# M_ch_Ph_t.net
KiCad netlist of a schematic drawn in Altium Designer
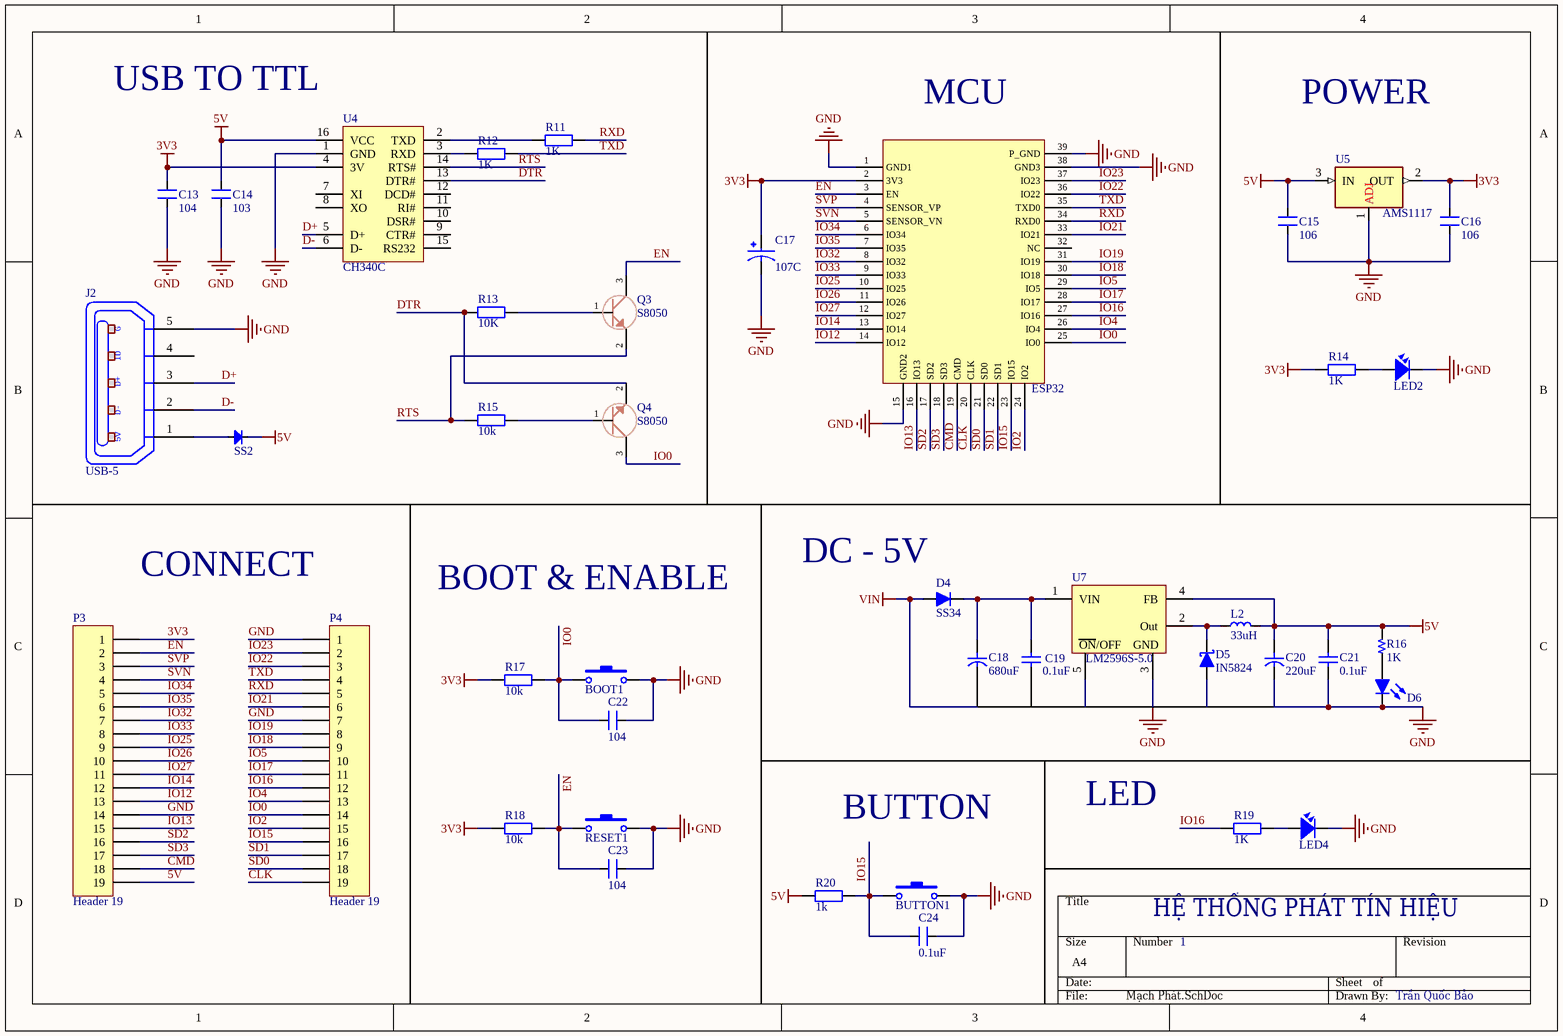
[diagram p0: Mạch Phát.SchDoc]

(export (version "E")
  (design (tool "Eeschema 10.0.6"))
  (components
    (comp (ref "BOOT1")
      (value "SW-SMD")
      (footprint "SW-SMD")
      (description "Switch")
      (fields (field (name "PUBLISHER") "Altium Limited"))
      (libsource (lib "My Library") (part "SW-SMD"))
    )
    (comp (ref "BUTTON1")
      (value "SW-SMD")
      (footprint "SW-SMD")
      (description "Switch")
      (fields (field (name "PUBLISHER") "Altium Limited"))
      (libsource (lib "My Library") (part "SW-SMD"))
    )
    (comp (ref "C13")
      (value "104")
      (footprint "SM-0805")
      (description "Cap SMD")
      (libsource (lib "My Library") (part "CM"))
    )
    (comp (ref "C14")
      (value "103")
      (footprint "SM-0805")
      (description "Cap SMD")
      (libsource (lib "My Library") (part "CM"))
    )
    (comp (ref "C15")
      (value "106")
      (footprint "SM-0805")
      (description "Cap SMD")
      (libsource (lib "My Library") (part "CM"))
    )
    (comp (ref "C16")
      (value "106")
      (footprint "SM-0805")
      (description "Cap SMD")
      (libsource (lib "My Library") (part "CM"))
    )
    (comp (ref "C17")
      (value "107C")
      (footprint "CAP_TANTALUM_3528")
      (description "Capacitor, Tantalum")
      (fields (field (name "MF") "AVX") (field (name "MP") "TAJB475K025RNJ"))
      (libsource (lib "My Library") (part "CAP_TANTALUM_SMD"))
    )
    (comp (ref "C18")
      (value "680uF")
      (footprint "C SMD TAN 1206 (A)")
      (description "Capacitor pol")
      (libsource (lib "chipfc_altium_libs") (part "Capacitor"))
    )
    (comp (ref "C19")
      (value "0.1uF")
      (footprint "C 0805")
      (description "Capacitor non-pol")
      (libsource (lib "chipfc_altium_libs") (part "Capacitor NP"))
    )
    (comp (ref "C20")
      (value "220uF")
      (footprint "C SMD TAN 1206 (A)")
      (description "Capacitor pol")
      (libsource (lib "chipfc_altium_libs") (part "Capacitor"))
    )
    (comp (ref "C21")
      (value "0.1uF")
      (footprint "C 0805")
      (description "Capacitor non-pol")
      (libsource (lib "chipfc_altium_libs") (part "Capacitor NP"))
    )
    (comp (ref "C22")
      (value "104")
      (footprint "SM-0805")
      (description "Cap SMD")
      (libsource (lib "My Library") (part "CM"))
    )
    (comp (ref "C23")
      (value "104")
      (footprint "SM-0805")
      (description "Cap SMD")
      (libsource (lib "My Library") (part "CM"))
    )
    (comp (ref "C24")
      (value "0.1uF")
      (footprint "SM-0805")
      (description "Cap SMD")
      (libsource (lib "My Library") (part "CM"))
    )
    (comp (ref "D4")
      (value "SS34")
      (footprint "DO-35 (SOD27 )")
      (description "Default Diode")
      (libsource (lib "chipfc_altium_libs") (part "Diode"))
    )
    (comp (ref "D5")
      (value "IN5824")
      (footprint "DO-41")
      (description "Schottky Diode")
      (libsource (lib "chipfc_altium_libs") (part "Diode Schottky"))
    )
    (comp (ref "D6")
      (value "Led")
      (footprint "Led 0805 RED")
      (description "Typical LED")
      (libsource (lib "chipfc_altium_libs") (part "Led"))
    )
    (comp (ref "ESP32")
      (value "ESP32")
      (footprint "My Library:ESP_WROOM_32")
      (libsource (lib "My Library") (part "ESP-WROOM-32"))
    )
    (comp (ref "J2")
      (value "USB-5")
      (footprint "USB-M1")
      (fields
        (field (name "MANUFACTURER") "FCI")
        (field (name "MANUFACTURER PART NUMBER") "10118193-0001LF")
        (field (name ".CREATOR") "MM")
        (field (name ".CHECKED PCB") "RF")
        (field (name ".CHECKED SCH") "MM")
      )
      (libsource (lib "My Library") (part "USB-5"))
    )
    (comp (ref "L2")
      (value "33uH")
      (footprint "Inductor SMD 12x12x8")
      (description "Inductor")
      (libsource (lib "chipfc_altium_libs") (part "Inductor"))
    )
    (comp (ref "LED2") (value "LED") (footprint "LED 3512") (libsource (lib "My Library") (part "LED SMD")))
    (comp (ref "LED4") (value "LED") (footprint "LED 3512") (libsource (lib "My Library") (part "LED SMD")))
    (comp (ref "P3")
      (value "Header 19")
      (footprint "HDR1X19")
      (description "Header, 19-Pin")
      (fields (field (name "PUBLISHER") "Altium Limited"))
      (libsource (lib "My Library") (part "Header 19"))
    )
    (comp (ref "P4")
      (value "Header 19")
      (footprint "HDR1X19")
      (description "Header, 19-Pin")
      (fields (field (name "PUBLISHER") "Altium Limited"))
      (libsource (lib "") (part "Header 19_1"))
    )
    (comp (ref "Q3")
      (value "S8050")
      (footprint "SOT23")
      (libsource (lib "My Library") (part "Transitor SMD"))
    )
    (comp (ref "Q4")
      (value "S8050")
      (footprint "SOT23")
      (libsource (lib "My Library") (part "Transitor SMD"))
    )
    (comp (ref "R11")
      (value "1K")
      (footprint "DIEN TRO 0805")
      (description "Resistor SMD 0805")
      (fields (field (name "Comment") "R0805") (field (name "PUBLISHER") "Altium Limited"))
      (libsource (lib "My Library") (part "R0805"))
    )
    (comp (ref "R12")
      (value "1K")
      (footprint "DIEN TRO 0805")
      (description "Resistor SMD 0805")
      (fields (field (name "Comment") "R0805") (field (name "PUBLISHER") "Altium Limited"))
      (libsource (lib "My Library") (part "R0805"))
    )
    (comp (ref "R13")
      (value "10K")
      (footprint "DIEN TRO 0805")
      (description "Resistor SMD 0805")
      (fields (field (name "Comment") "R0805") (field (name "PUBLISHER") "Altium Limited"))
      (libsource (lib "My Library") (part "R0805"))
    )
    (comp (ref "R14")
      (value "1K")
      (footprint "DIEN TRO 0805")
      (description "Resistor SMD 0805")
      (fields (field (name "Comment") "R0805") (field (name "PUBLISHER") "Altium Limited"))
      (libsource (lib "My Library") (part "R0805"))
    )
    (comp (ref "R15")
      (value "10k")
      (footprint "DIEN TRO 0805")
      (description "Resistor SMD 0805")
      (fields (field (name "Comment") "R0805") (field (name "PUBLISHER") "Altium Limited"))
      (libsource (lib "My Library") (part "R0805"))
    )
    (comp (ref "R16")
      (value "1K")
      (footprint "R 0805")
      (description "Resistor")
      (libsource (lib "chipfc_altium_libs") (part "Resistor"))
    )
    (comp (ref "R17")
      (value "10k")
      (footprint "DIEN TRO 0805")
      (description "Resistor SMD 0805")
      (fields (field (name "Comment") "R0805") (field (name "PUBLISHER") "Altium Limited"))
      (libsource (lib "My Library") (part "R0805"))
    )
    (comp (ref "R18")
      (value "10k")
      (footprint "DIEN TRO 0805")
      (description "Resistor SMD 0805")
      (fields (field (name "Comment") "R0805") (field (name "PUBLISHER") "Altium Limited"))
      (libsource (lib "My Library") (part "R0805"))
    )
    (comp (ref "R19")
      (value "1K")
      (footprint "DIEN TRO 0805")
      (description "Resistor SMD 0805")
      (fields (field (name "Comment") "R0805") (field (name "PUBLISHER") "Altium Limited"))
      (libsource (lib "My Library") (part "R0805"))
    )
    (comp (ref "R20")
      (value "1k")
      (footprint "DIEN TRO 0805")
      (description "Resistor SMD 0805")
      (fields (field (name "Comment") "R0805") (field (name "PUBLISHER") "Altium Limited"))
      (libsource (lib "My Library") (part "R0805"))
    )
    (comp (ref "RESET1")
      (value "SW-SMD")
      (footprint "SW-SMD")
      (description "Switch")
      (fields (field (name "PUBLISHER") "Altium Limited"))
      (libsource (lib "My Library") (part "SW-SMD"))
    )
    (comp (ref "SS2")
      (value "Diode SMD")
      (footprint "DIO-SMD-106")
      (description "Default Diode")
      (fields (field (name "PUBLISHER") "Altium Limited"))
      (libsource (lib "My Library") (part "Diode SMD"))
    )
    (comp (ref "U4")
      (value "CH340C")
      (footprint "SO16")
      (description "High and Low Side Driver")
      (fields (field (name "PUBLISHER") "Altium Limited"))
      (libsource (lib "My Library") (part "CH340G"))
    )
    (comp (ref "U5")
      (value "AMS1117")
      (footprint "SOT223-4N")
      (description "IC")
      (libsource (lib "My Library") (part "AMS1117"))
    )
    (comp (ref "U7")
      (value "LM2596S-5.0")
      (footprint "TO-263-5")
      (description "Simple Switcher 3A Step-Down Voltage Regulator")
      (libsource (lib "chipfc_altium_libs") (part "LM2596S-5.0"))
    )
  )
  (nets
    (net (code "1") (name "/CLK") (class "Default")
      (node (ref "ESP32") (pin "20") (pinfunction "CLK_20") (pintype "passive"))
      (node (ref "P4") (pin "19") (pinfunction "19_19") (pintype "passive"))
    )
    (net (code "2") (name "/CMD") (class "Default")
      (node (ref "ESP32") (pin "19") (pinfunction "CMD_19") (pintype "passive"))
      (node (ref "P3") (pin "18") (pinfunction "18_18") (pintype "passive"))
    )
    (net (code "3") (name "/D+") (class "Default")
      (node (ref "J2") (pin "3") (pinfunction "P3_3") (pintype "passive"))
      (node (ref "U4") (pin "5") (pinfunction "D+_5") (pintype "passive"))
    )
    (net (code "4") (name "/D-") (class "Default")
      (node (ref "J2") (pin "2") (pinfunction "P2_2") (pintype "passive"))
      (node (ref "U4") (pin "6") (pinfunction "D-_6") (pintype "passive"))
    )
    (net (code "5") (name "/DTR") (class "Default")
      (node (ref "Q4") (pin "2") (pinfunction "E_2") (pintype "passive"))
      (node (ref "R13") (pin "1") (pinfunction "1_1") (pintype "passive"))
      (node (ref "U4") (pin "13") (pinfunction "DTR#_13") (pintype "passive"))
    )
    (net (code "6") (name "/EN") (class "Default")
      (node (ref "C23") (pin "2") (pinfunction "2_2") (pintype "passive"))
      (node (ref "ESP32") (pin "3") (pinfunction "EN_3") (pintype "passive"))
      (node (ref "P3") (pin "2") (pinfunction "2_2") (pintype "passive"))
      (node (ref "Q3") (pin "3") (pinfunction "C_3") (pintype "passive"))
      (node (ref "R18") (pin "2") (pinfunction "2_2") (pintype "passive"))
      (node (ref "RESET1") (pin "1") (pinfunction "1_1") (pintype "passive"))
    )
    (net (code "7") (name "/IO0") (class "Default")
      (node (ref "BOOT1") (pin "1") (pinfunction "1_1") (pintype "passive"))
      (node (ref "C22") (pin "2") (pinfunction "2_2") (pintype "passive"))
      (node (ref "ESP32") (pin "25") (pinfunction "IO0_25") (pintype "passive"))
      (node (ref "P4") (pin "14") (pinfunction "14_14") (pintype "passive"))
      (node (ref "Q4") (pin "3") (pinfunction "C_3") (pintype "passive"))
      (node (ref "R17") (pin "2") (pinfunction "2_2") (pintype "passive"))
    )
    (net (code "8") (name "/IO2") (class "Default")
      (node (ref "ESP32") (pin "24") (pinfunction "IO2_24") (pintype "passive"))
      (node (ref "P4") (pin "15") (pinfunction "15_15") (pintype "passive"))
    )
    (net (code "9") (name "/IO4") (class "Default")
      (node (ref "ESP32") (pin "26") (pinfunction "IO4_26") (pintype "passive"))
      (node (ref "P4") (pin "13") (pinfunction "13_13") (pintype "passive"))
    )
    (net (code "10") (name "/IO5") (class "Default")
      (node (ref "ESP32") (pin "29") (pinfunction "IO5_29") (pintype "passive"))
      (node (ref "P4") (pin "10") (pinfunction "10_10") (pintype "passive"))
    )
    (net (code "11") (name "/IO12") (class "Default")
      (node (ref "ESP32") (pin "14") (pinfunction "IO12_14") (pintype "passive"))
      (node (ref "P3") (pin "13") (pinfunction "13_13") (pintype "passive"))
    )
    (net (code "12") (name "/IO13") (class "Default")
      (node (ref "ESP32") (pin "16") (pinfunction "IO13_16") (pintype "passive"))
      (node (ref "P3") (pin "15") (pinfunction "15_15") (pintype "passive"))
    )
    (net (code "13") (name "/IO14") (class "Default")
      (node (ref "ESP32") (pin "13") (pinfunction "IO14_13") (pintype "passive"))
      (node (ref "P3") (pin "12") (pinfunction "12_12") (pintype "passive"))
    )
    (net (code "14") (name "/IO15") (class "Default")
      (node (ref "BUTTON1") (pin "1") (pinfunction "1_1") (pintype "passive"))
      (node (ref "C24") (pin "2") (pinfunction "2_2") (pintype "passive"))
      (node (ref "ESP32") (pin "23") (pinfunction "IO15_23") (pintype "passive"))
      (node (ref "P4") (pin "16") (pinfunction "16_16") (pintype "passive"))
      (node (ref "R20") (pin "2") (pinfunction "2_2") (pintype "passive"))
    )
    (net (code "15") (name "/IO16") (class "Default")
      (node (ref "ESP32") (pin "27") (pinfunction "IO16_27") (pintype "passive"))
      (node (ref "P4") (pin "12") (pinfunction "12_12") (pintype "passive"))
      (node (ref "R19") (pin "1") (pinfunction "1_1") (pintype "passive"))
    )
    (net (code "16") (name "/IO17") (class "Default")
      (node (ref "ESP32") (pin "28") (pinfunction "IO17_28") (pintype "passive"))
      (node (ref "P4") (pin "11") (pinfunction "11_11") (pintype "passive"))
    )
    (net (code "17") (name "/IO18") (class "Default")
      (node (ref "ESP32") (pin "30") (pinfunction "IO18_30") (pintype "passive"))
      (node (ref "P4") (pin "9") (pinfunction "9_9") (pintype "passive"))
    )
    (net (code "18") (name "/IO19") (class "Default")
      (node (ref "ESP32") (pin "31") (pinfunction "IO19_31") (pintype "passive"))
      (node (ref "P4") (pin "8") (pinfunction "8_8") (pintype "passive"))
    )
    (net (code "19") (name "/IO21") (class "Default")
      (node (ref "ESP32") (pin "33") (pinfunction "IO21_33") (pintype "passive"))
      (node (ref "P4") (pin "6") (pinfunction "6_6") (pintype "passive"))
    )
    (net (code "20") (name "/IO22") (class "Default")
      (node (ref "ESP32") (pin "36") (pinfunction "IO22_36") (pintype "passive"))
      (node (ref "P4") (pin "3") (pinfunction "3_3") (pintype "passive"))
    )
    (net (code "21") (name "/IO23") (class "Default")
      (node (ref "ESP32") (pin "37") (pinfunction "IO23_37") (pintype "passive"))
      (node (ref "P4") (pin "2") (pinfunction "2_2") (pintype "passive"))
    )
    (net (code "22") (name "/IO25") (class "Default")
      (node (ref "ESP32") (pin "10") (pinfunction "IO25_10") (pintype "passive"))
      (node (ref "P3") (pin "9") (pinfunction "9_9") (pintype "passive"))
    )
    (net (code "23") (name "/IO26") (class "Default")
      (node (ref "ESP32") (pin "11") (pinfunction "IO26_11") (pintype "passive"))
      (node (ref "P3") (pin "10") (pinfunction "10_10") (pintype "passive"))
    )
    (net (code "24") (name "/IO27") (class "Default")
      (node (ref "ESP32") (pin "12") (pinfunction "IO27_12") (pintype "passive"))
      (node (ref "P3") (pin "11") (pinfunction "11_11") (pintype "passive"))
    )
    (net (code "25") (name "/IO32") (class "Default")
      (node (ref "ESP32") (pin "8") (pinfunction "IO32_8") (pintype "passive"))
      (node (ref "P3") (pin "7") (pinfunction "7_7") (pintype "passive"))
    )
    (net (code "26") (name "/IO33") (class "Default")
      (node (ref "ESP32") (pin "9") (pinfunction "IO33_9") (pintype "passive"))
      (node (ref "P3") (pin "8") (pinfunction "8_8") (pintype "passive"))
    )
    (net (code "27") (name "/IO34") (class "Default")
      (node (ref "ESP32") (pin "6") (pinfunction "IO34_6") (pintype "passive"))
      (node (ref "P3") (pin "5") (pinfunction "5_5") (pintype "passive"))
    )
    (net (code "28") (name "/IO35") (class "Default")
      (node (ref "ESP32") (pin "7") (pinfunction "IO35_7") (pintype "passive"))
      (node (ref "P3") (pin "6") (pinfunction "6_6") (pintype "passive"))
    )
    (net (code "29") (name "/RTS") (class "Default")
      (node (ref "Q3") (pin "2") (pinfunction "E_2") (pintype "passive"))
      (node (ref "R15") (pin "1") (pinfunction "1_1") (pintype "passive"))
      (node (ref "U4") (pin "14") (pinfunction "RTS#_14") (pintype "passive"))
    )
    (net (code "30") (name "/RXD") (class "Default")
      (node (ref "ESP32") (pin "34") (pinfunction "RXD0_34") (pintype "passive"))
      (node (ref "P4") (pin "5") (pinfunction "5_5") (pintype "passive"))
      (node (ref "R11") (pin "2") (pinfunction "2_2") (pintype "passive"))
    )
    (net (code "31") (name "/SD0") (class "Default")
      (node (ref "ESP32") (pin "21") (pinfunction "SD0_21") (pintype "passive"))
      (node (ref "P4") (pin "18") (pinfunction "18_18") (pintype "passive"))
    )
    (net (code "32") (name "/SD1") (class "Default")
      (node (ref "ESP32") (pin "22") (pinfunction "SD1_22") (pintype "passive"))
      (node (ref "P4") (pin "17") (pinfunction "17_17") (pintype "passive"))
    )
    (net (code "33") (name "/SD2") (class "Default")
      (node (ref "ESP32") (pin "17") (pinfunction "SD2_17") (pintype "passive"))
      (node (ref "P3") (pin "16") (pinfunction "16_16") (pintype "passive"))
    )
    (net (code "34") (name "/SD3") (class "Default")
      (node (ref "ESP32") (pin "18") (pinfunction "SD3_18") (pintype "passive"))
      (node (ref "P3") (pin "17") (pinfunction "17_17") (pintype "passive"))
    )
    (net (code "35") (name "/SVN") (class "Default")
      (node (ref "ESP32") (pin "5") (pinfunction "SENSOR_VN_5") (pintype "passive"))
      (node (ref "P3") (pin "4") (pinfunction "4_4") (pintype "passive"))
    )
    (net (code "36") (name "/SVP") (class "Default")
      (node (ref "ESP32") (pin "4") (pinfunction "SENSOR_VP_4") (pintype "passive"))
      (node (ref "P3") (pin "3") (pinfunction "3_3") (pintype "passive"))
    )
    (net (code "37") (name "/TXD") (class "Default")
      (node (ref "ESP32") (pin "35") (pinfunction "TXD0_35") (pintype "passive"))
      (node (ref "P4") (pin "4") (pinfunction "4_4") (pintype "passive"))
      (node (ref "R12") (pin "2") (pinfunction "2_2") (pintype "passive"))
    )
    (net (code "38") (name "3V3") (class "Default")
      (node (ref "C13") (pin "2") (pinfunction "2_2") (pintype "passive"))
      (node (ref "C16") (pin "2") (pinfunction "2_2") (pintype "passive"))
      (node (ref "C17") (pin "1") (pinfunction "1_1") (pintype "passive"))
      (node (ref "ESP32") (pin "2") (pinfunction "3V3_2") (pintype "passive"))
      (node (ref "P3") (pin "1") (pinfunction "1_1") (pintype "passive"))
      (node (ref "R14") (pin "1") (pinfunction "1_1") (pintype "passive"))
      (node (ref "R17") (pin "1") (pinfunction "1_1") (pintype "passive"))
      (node (ref "R18") (pin "1") (pinfunction "1_1") (pintype "passive"))
      (node (ref "U4") (pin "4") (pinfunction "3V_4") (pintype "passive"))
      (node (ref "U5") (pin "2") (pinfunction "OUT_2") (pintype "output"))
    )
    (net (code "39") (name "5V") (class "Default")
      (node (ref "C14") (pin "2") (pinfunction "2_2") (pintype "passive"))
      (node (ref "C15") (pin "2") (pinfunction "2_2") (pintype "passive"))
      (node (ref "C20") (pin "1") (pinfunction "1_1") (pintype "passive"))
      (node (ref "C21") (pin "1") (pinfunction "1_1") (pintype "passive"))
      (node (ref "L2") (pin "2") (pinfunction "2_2") (pintype "passive"))
      (node (ref "P3") (pin "19") (pinfunction "19_19") (pintype "passive"))
      (node (ref "R16") (pin "2") (pinfunction "2_2") (pintype "passive"))
      (node (ref "R20") (pin "1") (pinfunction "1_1") (pintype "passive"))
      (node (ref "SS2") (pin "2") (pinfunction "K_2") (pintype "passive"))
      (node (ref "U4") (pin "16") (pinfunction "VCC_16") (pintype "passive"))
      (node (ref "U5") (pin "3") (pinfunction "IN_3") (pintype "input"))
      (node (ref "U7") (pin "4") (pinfunction "FB_4") (pintype "passive"))
    )
    (net (code "40") (name "GND") (class "Default")
      (node (ref "BOOT1") (pin "2") (pinfunction "2_2") (pintype "passive"))
      (node (ref "BUTTON1") (pin "2") (pinfunction "2_2") (pintype "passive"))
      (node (ref "C13") (pin "1") (pinfunction "1_1") (pintype "passive"))
      (node (ref "C14") (pin "1") (pinfunction "1_1") (pintype "passive"))
      (node (ref "C15") (pin "1") (pinfunction "1_1") (pintype "passive"))
      (node (ref "C16") (pin "1") (pinfunction "1_1") (pintype "passive"))
      (node (ref "C17") (pin "2") (pinfunction "2_2") (pintype "passive"))
      (node (ref "C20") (pin "2") (pinfunction "2_2") (pintype "passive"))
      (node (ref "C21") (pin "2") (pinfunction "2_2") (pintype "passive"))
      (node (ref "C22") (pin "1") (pinfunction "1_1") (pintype "passive"))
      (node (ref "C23") (pin "1") (pinfunction "1_1") (pintype "passive"))
      (node (ref "C24") (pin "1") (pinfunction "1_1") (pintype "passive"))
      (node (ref "D6") (pin "2") (pinfunction "K_2") (pintype "passive"))
      (node (ref "ESP32") (pin "1") (pinfunction "GND1_1") (pintype "passive"))
      (node (ref "ESP32") (pin "15") (pinfunction "GND2_15") (pintype "passive"))
      (node (ref "ESP32") (pin "38") (pinfunction "GND3_38") (pintype "passive"))
      (node (ref "ESP32") (pin "39") (pinfunction "P_GND_39") (pintype "passive"))
      (node (ref "J2") (pin "5") (pinfunction "P5_5") (pintype "passive"))
      (node (ref "LED2") (pin "2") (pinfunction "2_2") (pintype "passive"))
      (node (ref "LED4") (pin "2") (pinfunction "2_2") (pintype "passive"))
      (node (ref "P3") (pin "14") (pinfunction "14_14") (pintype "passive"))
      (node (ref "P4") (pin "1") (pinfunction "1_1") (pintype "passive"))
      (node (ref "P4") (pin "7") (pinfunction "7_7") (pintype "passive"))
      (node (ref "RESET1") (pin "2") (pinfunction "2_2") (pintype "passive"))
      (node (ref "U4") (pin "1") (pinfunction "GND_1") (pintype "passive"))
      (node (ref "U5") (pin "1") (pinfunction "ADJ_1") (pintype "passive"))
      (node (ref "U7") (pin "3") (pinfunction "GND_3") (pintype "passive"))
    )
    (net (code "41") (name "Net-(D4-K)") (class "Default")
      (node (ref "C18") (pin "1") (pinfunction "1_1") (pintype "passive"))
      (node (ref "C19") (pin "1") (pinfunction "1_1") (pintype "passive"))
      (node (ref "D4") (pin "2") (pinfunction "K_2") (pintype "passive"))
      (node (ref "U7") (pin "1") (pinfunction "VIN_1") (pintype "passive"))
    )
    (net (code "42") (name "Net-(D5-K)") (class "Default")
      (node (ref "D5") (pin "2") (pinfunction "K_2") (pintype "passive"))
      (node (ref "L2") (pin "1") (pinfunction "1_1") (pintype "passive"))
      (node (ref "U7") (pin "2") (pinfunction "Out_2") (pintype "passive"))
    )
    (net (code "43") (name "Net-(D6-A)") (class "Default")
      (node (ref "D6") (pin "1") (pinfunction "A_1") (pintype "passive"))
      (node (ref "R16") (pin "1") (pinfunction "1_1") (pintype "passive"))
    )
    (net (code "44") (name "Net-(J2-P1)") (class "Default")
      (node (ref "J2") (pin "1") (pinfunction "P1_1") (pintype "passive"))
      (node (ref "SS2") (pin "1") (pinfunction "A_1") (pintype "passive"))
    )
    (net (code "45") (name "Net-(LED2-Pad1)") (class "Default")
      (node (ref "LED2") (pin "1") (pinfunction "1_1") (pintype "passive"))
      (node (ref "R14") (pin "2") (pinfunction "2_2") (pintype "passive"))
    )
    (net (code "46") (name "Net-(LED4-Pad1)") (class "Default")
      (node (ref "LED4") (pin "1") (pinfunction "1_1") (pintype "passive"))
      (node (ref "R19") (pin "2") (pinfunction "2_2") (pintype "passive"))
    )
    (net (code "47") (name "Net-(Q3-B)") (class "Default")
      (node (ref "Q3") (pin "1") (pinfunction "B_1") (pintype "passive"))
      (node (ref "R13") (pin "2") (pinfunction "2_2") (pintype "passive"))
    )
    (net (code "48") (name "Net-(Q4-B)") (class "Default")
      (node (ref "Q4") (pin "1") (pinfunction "B_1") (pintype "passive"))
      (node (ref "R15") (pin "2") (pinfunction "2_2") (pintype "passive"))
    )
    (net (code "49") (name "Net-(U4-RXD)") (class "Default")
      (node (ref "R12") (pin "1") (pinfunction "1_1") (pintype "passive"))
      (node (ref "U4") (pin "3") (pinfunction "RXD_3") (pintype "passive"))
    )
    (net (code "50") (name "Net-(U4-TXD)") (class "Default")
      (node (ref "R11") (pin "1") (pinfunction "1_1") (pintype "passive"))
      (node (ref "U4") (pin "2") (pinfunction "TXD_2") (pintype "passive"))
    )
    (net (code "51") (name "VIN") (class "Default")
      (node (ref "D4") (pin "1") (pinfunction "A_1") (pintype "passive"))
    )
    (net (code "52") (name "unconnected-(C18-Pad2)") (class "Default")
      (node (ref "C18") (pin "2") (pinfunction "2_2") (pintype "passive"))
    )
    (net (code "53") (name "unconnected-(C19-Pad2)") (class "Default")
      (node (ref "C19") (pin "2") (pinfunction "2_2") (pintype "passive"))
    )
    (net (code "54") (name "unconnected-(D5-A-Pad1)") (class "Default")
      (node (ref "D5") (pin "1") (pinfunction "A_1") (pintype "passive"))
    )
    (net (code "55") (name "unconnected-(ESP32-NC-Pad32)") (class "Default")
      (node (ref "ESP32") (pin "32") (pinfunction "NC_32") (pintype "passive"))
    )
    (net (code "56") (name "unconnected-(J2-P4-Pad4)") (class "Default")
      (node (ref "J2") (pin "4") (pinfunction "P4_4") (pintype "passive"))
    )
    (net (code "57") (name "unconnected-(U4-CTR#-Pad9)") (class "Default")
      (node (ref "U4") (pin "9") (pinfunction "CTR#_9") (pintype "passive"))
    )
    (net (code "58") (name "unconnected-(U4-DCD#-Pad12)") (class "Default")
      (node (ref "U4") (pin "12") (pinfunction "DCD#_12") (pintype "passive"))
    )
    (net (code "59") (name "unconnected-(U4-DSR#-Pad10)") (class "Default")
      (node (ref "U4") (pin "10") (pinfunction "DSR#_10") (pintype "passive"))
    )
    (net (code "60") (name "unconnected-(U4-RI#-Pad11)") (class "Default")
      (node (ref "U4") (pin "11") (pinfunction "RI#_11") (pintype "passive"))
    )
    (net (code "61") (name "unconnected-(U4-RS232-Pad15)") (class "Default")
      (node (ref "U4") (pin "15") (pinfunction "RS232_15") (pintype "passive"))
    )
    (net (code "62") (name "unconnected-(U4-XI-Pad7)") (class "Default")
      (node (ref "U4") (pin "7") (pinfunction "XI_7") (pintype "passive"))
    )
    (net (code "63") (name "unconnected-(U4-XO-Pad8)") (class "Default")
      (node (ref "U4") (pin "8") (pinfunction "XO_8") (pintype "passive"))
    )
    (net (code "64") (name "unconnected-(U7-PAD-Pad6)") (class "Default")
      (node (ref "U7") (pin "6") (pinfunction "PAD_6") (pintype "passive"))
    )
    (net (code "65") (name "unconnected-(U7-~{ON}{slash}OFF-Pad5)") (class "Default")
      (node (ref "U7") (pin "5") (pinfunction "~{ON}/OFF_5") (pintype "passive"))
    )
  )
)
